# HVPowerSupply.net
KiCad netlist of a schematic drawn in Altium Designer
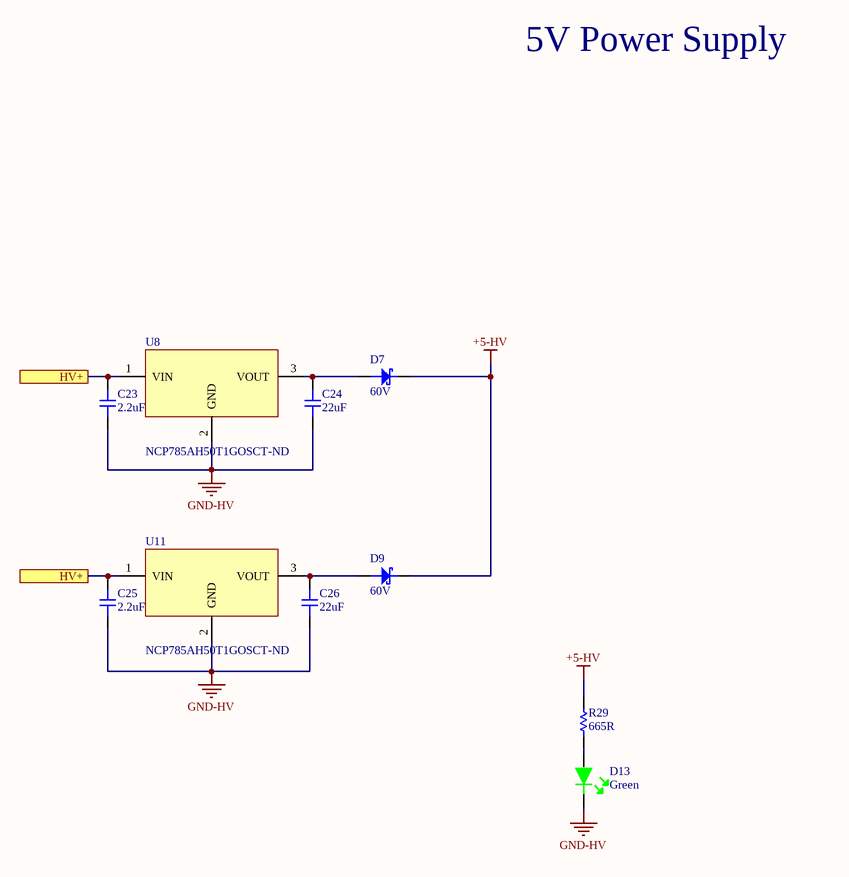
[diagram p0: HVPowerSupply.SchDoc]

(export (version "E")
  (design (tool "Eeschema 10.0.6"))
  (components
    (comp (ref "C23")
      (value "2.2uF")
      (footprint "CAP-2220")
      (description "CAP CER 2.2UF 450V X6S 2220")
      (fields
        (field (name "MANUFACTURER") "TDK")
        (field (name "MANUFACTURER PART NUMBER") "C5750X6S2W225K250KA")
      )
      (libsource (lib "Capacitors") (part "2220-2.2uF-450V"))
    )
    (comp (ref "C24")
      (value "22uF")
      (footprint "CAP-0805")
      (description "CAP CER 22UF 10V X5R 0805")
      (fields
        (field (name "MANUFACTURER") "KEMET")
        (field (name "MANUFACTURER PART NUMBER") "C0805C226M8PACTU")
      )
      (libsource (lib "Capacitors") (part "0805-22uF-10V"))
    )
    (comp (ref "C25")
      (value "2.2uF")
      (footprint "CAP-2220")
      (description "CAP CER 2.2UF 450V X6S 2220")
      (fields
        (field (name "MANUFACTURER") "TDK")
        (field (name "MANUFACTURER PART NUMBER") "C5750X6S2W225K250KA")
      )
      (libsource (lib "Capacitors") (part "2220-2.2uF-450V"))
    )
    (comp (ref "C26")
      (value "22uF")
      (footprint "CAP-0805")
      (description "CAP CER 22UF 10V X5R 0805")
      (fields
        (field (name "MANUFACTURER") "KEMET")
        (field (name "MANUFACTURER PART NUMBER") "C0805C226M8PACTU")
      )
      (libsource (lib "Capacitors") (part "0805-22uF-10V"))
    )
    (comp (ref "D7")
      (value "60V")
      (footprint "Diode-SOD123W")
      (description "DIODE SCHOTTKY 60V 2A SOD123W")
      (fields
        (field (name "MANUFACTURER") "Nexperia")
        (field (name "MANUFACTURER PART NUMBER") "PMEG6020ER,115")
      )
      (libsource (lib "Diodes") (part "Schottky-60V-2A"))
    )
    (comp (ref "D9")
      (value "60V")
      (footprint "Diode-SOD123W")
      (description "DIODE SCHOTTKY 60V 2A SOD123W")
      (fields
        (field (name "MANUFACTURER") "Nexperia")
        (field (name "MANUFACTURER PART NUMBER") "PMEG6020ER,115")
      )
      (libsource (lib "Diodes") (part "Schottky-60V-2A"))
    )
    (comp (ref "D13")
      (value "Green")
      (footprint "LED-0603")
      (description "LED GREEN CLEAR 0603 SMD")
      (fields
        (field (name "MANUFACTURER") "Wurth Electronics")
        (field (name "MANUFACTURER PART NUMBER") "150060VS75000")
      )
      (libsource (lib "LEDs") (part "LED-Green"))
    )
    (comp (ref "R29")
      (value "665R")
      (footprint "RES-0805")
      (description "RES SMD 665 OHM 1% 1/8W 0805")
      (fields
        (field (name "MANUFACTURER") "Panasonic")
        (field (name "MANUFACTURER PART NUMBER") "ERJ-6ENF6650V")
      )
      (libsource (lib "Resistors") (part "0805-665R"))
    )
    (comp (ref "U8")
      (value "NCP785AH50T1GOSCT-ND")
      (footprint "SOT-89")
      (description "IC REG LINEAR  5V 10MA SOT89-3")
      (fields
        (field (name "MANUFACTURER") "ON Semiconductor")
        (field (name "MANUFACTURER PART NUMBER") "NCP785AH50T1G")
      )
      (libsource (lib "Power") (part "LDO-5V-10mA"))
    )
    (comp (ref "U11")
      (value "NCP785AH50T1GOSCT-ND")
      (footprint "SOT-89")
      (description "IC REG LINEAR  5V 10MA SOT89-3")
      (fields
        (field (name "MANUFACTURER") "ON Semiconductor")
        (field (name "MANUFACTURER PART NUMBER") "NCP785AH50T1G")
      )
      (libsource (lib "Power") (part "LDO-5V-10mA"))
    )
  )
  (nets
    (net (code "1") (name "+5-HV") (class "Default")
      (node (ref "D7") (pin "1") (pinfunction "1_1") (pintype "passive"))
      (node (ref "D9") (pin "1") (pinfunction "1_1") (pintype "passive"))
      (node (ref "R29") (pin "2") (pinfunction "2_2") (pintype "passive"))
    )
    (net (code "2") (name "/HV+") (class "Default")
      (node (ref "C23") (pin "2") (pinfunction "2_2") (pintype "passive"))
      (node (ref "C25") (pin "2") (pinfunction "2_2") (pintype "passive"))
      (node (ref "U11") (pin "1") (pinfunction "VIN_1") (pintype "passive"))
      (node (ref "U8") (pin "1") (pinfunction "VIN_1") (pintype "passive"))
    )
    (net (code "3") (name "GND-HV") (class "Default")
      (node (ref "C23") (pin "1") (pinfunction "1_1") (pintype "passive"))
      (node (ref "C24") (pin "1") (pinfunction "1_1") (pintype "passive"))
      (node (ref "C25") (pin "1") (pinfunction "1_1") (pintype "passive"))
      (node (ref "C26") (pin "1") (pinfunction "1_1") (pintype "passive"))
      (node (ref "D13") (pin "2") (pinfunction "2_2") (pintype "passive"))
      (node (ref "U11") (pin "2") (pinfunction "GND_2") (pintype "passive"))
      (node (ref "U8") (pin "2") (pinfunction "GND_2") (pintype "passive"))
    )
    (net (code "4") (name "Net-(D13-Pad1)") (class "Default")
      (node (ref "D13") (pin "1") (pinfunction "1_1") (pintype "passive"))
      (node (ref "R29") (pin "1") (pinfunction "1_1") (pintype "passive"))
    )
    (net (code "5") (name "Net-(U8-VOUT)") (class "Default")
      (node (ref "C24") (pin "2") (pinfunction "2_2") (pintype "passive"))
      (node (ref "D7") (pin "2") (pinfunction "2_2") (pintype "passive"))
      (node (ref "U8") (pin "3") (pinfunction "VOUT_3") (pintype "passive"))
    )
    (net (code "6") (name "Net-(U11-VOUT)") (class "Default")
      (node (ref "C26") (pin "2") (pinfunction "2_2") (pintype "passive"))
      (node (ref "D9") (pin "2") (pinfunction "2_2") (pintype "passive"))
      (node (ref "U11") (pin "3") (pinfunction "VOUT_3") (pintype "passive"))
    )
  )
)
